# CCM_0010.net
KiCad netlist of a schematic drawn in EAGLE
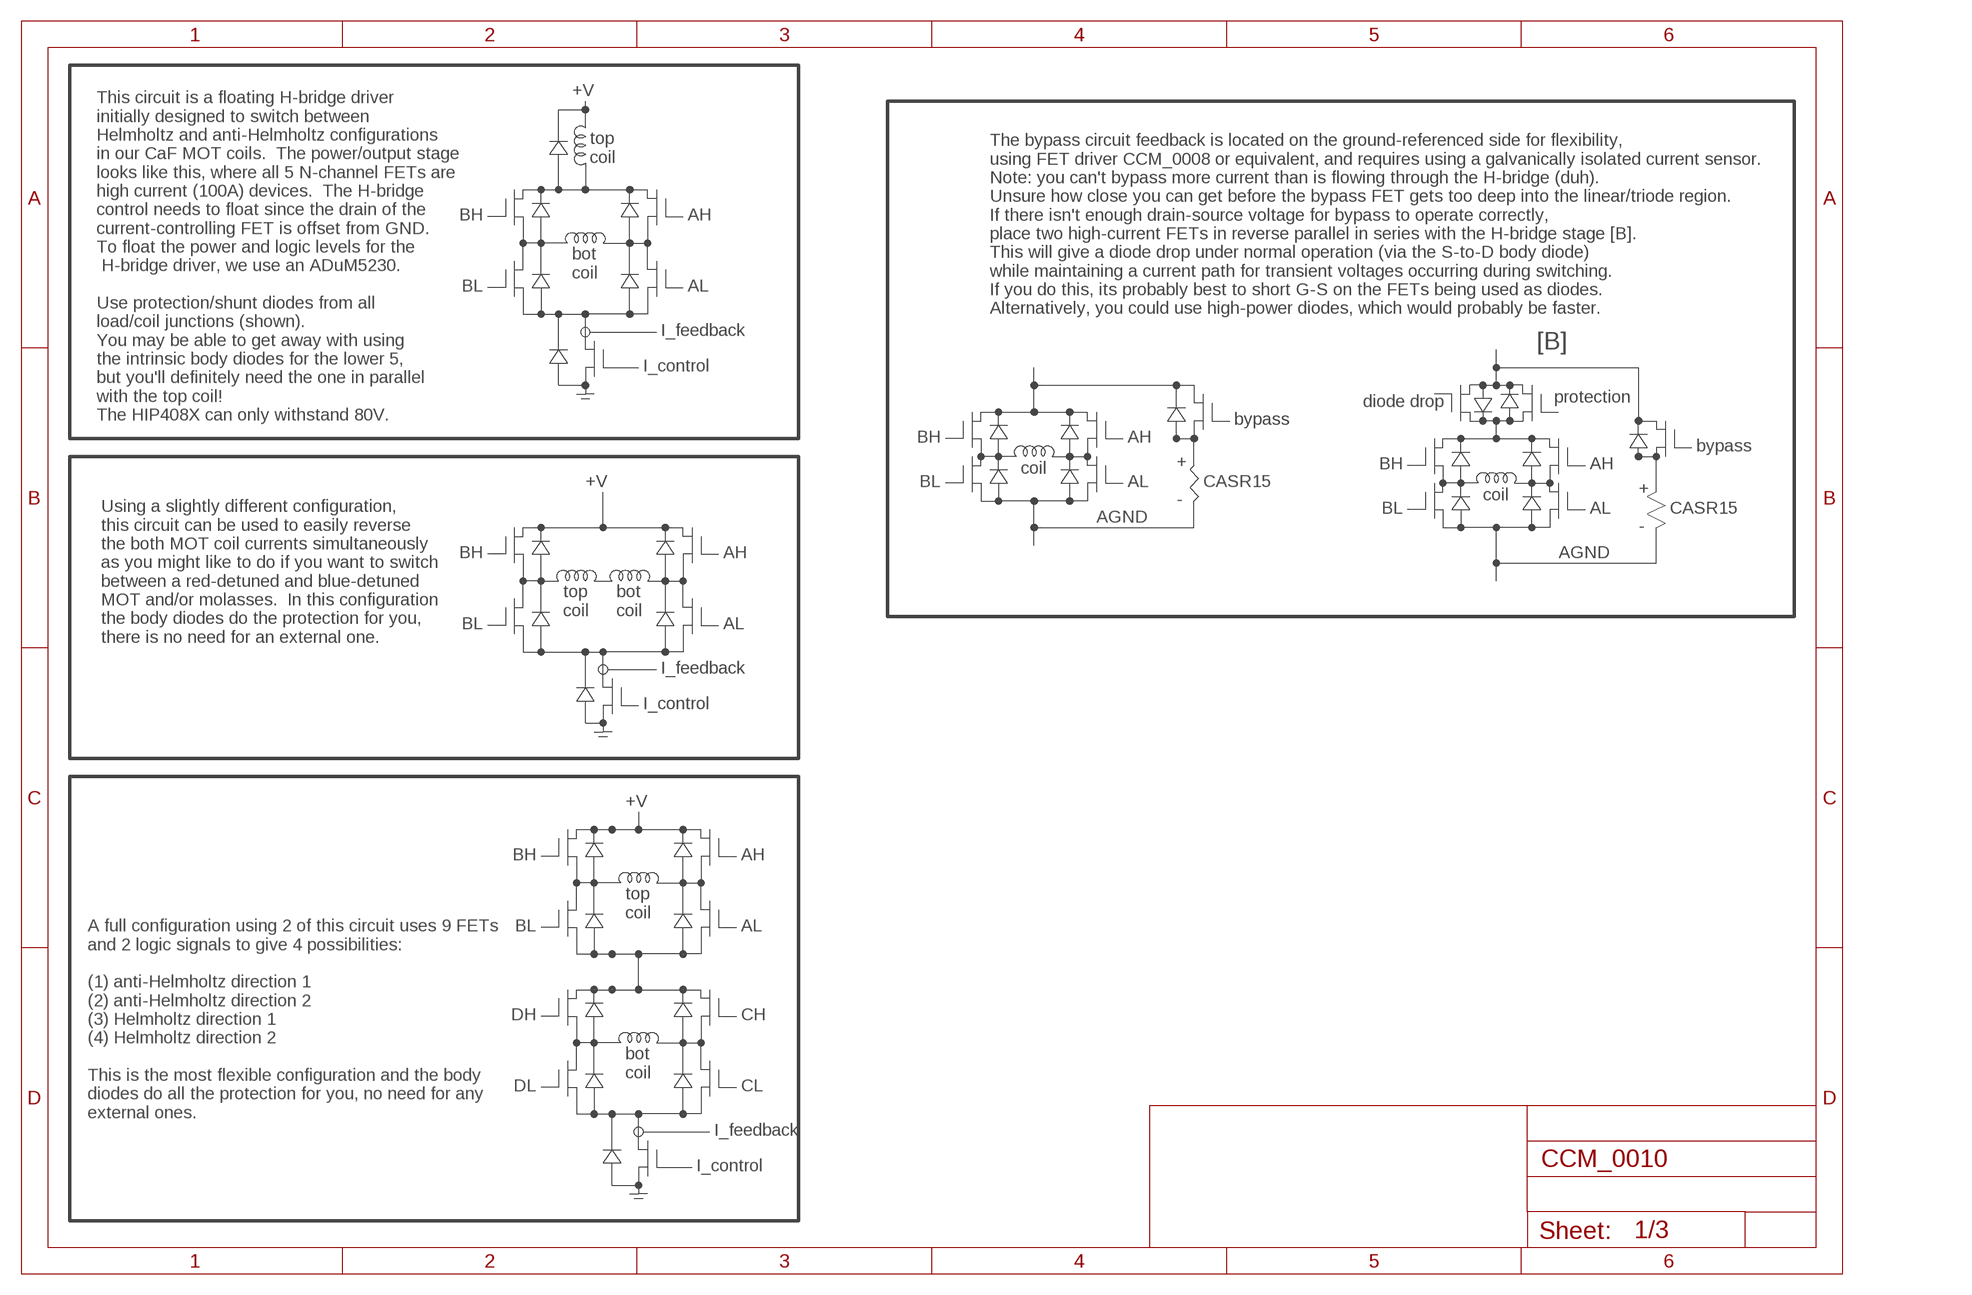
[diagram p0: schematic, sheet 1]
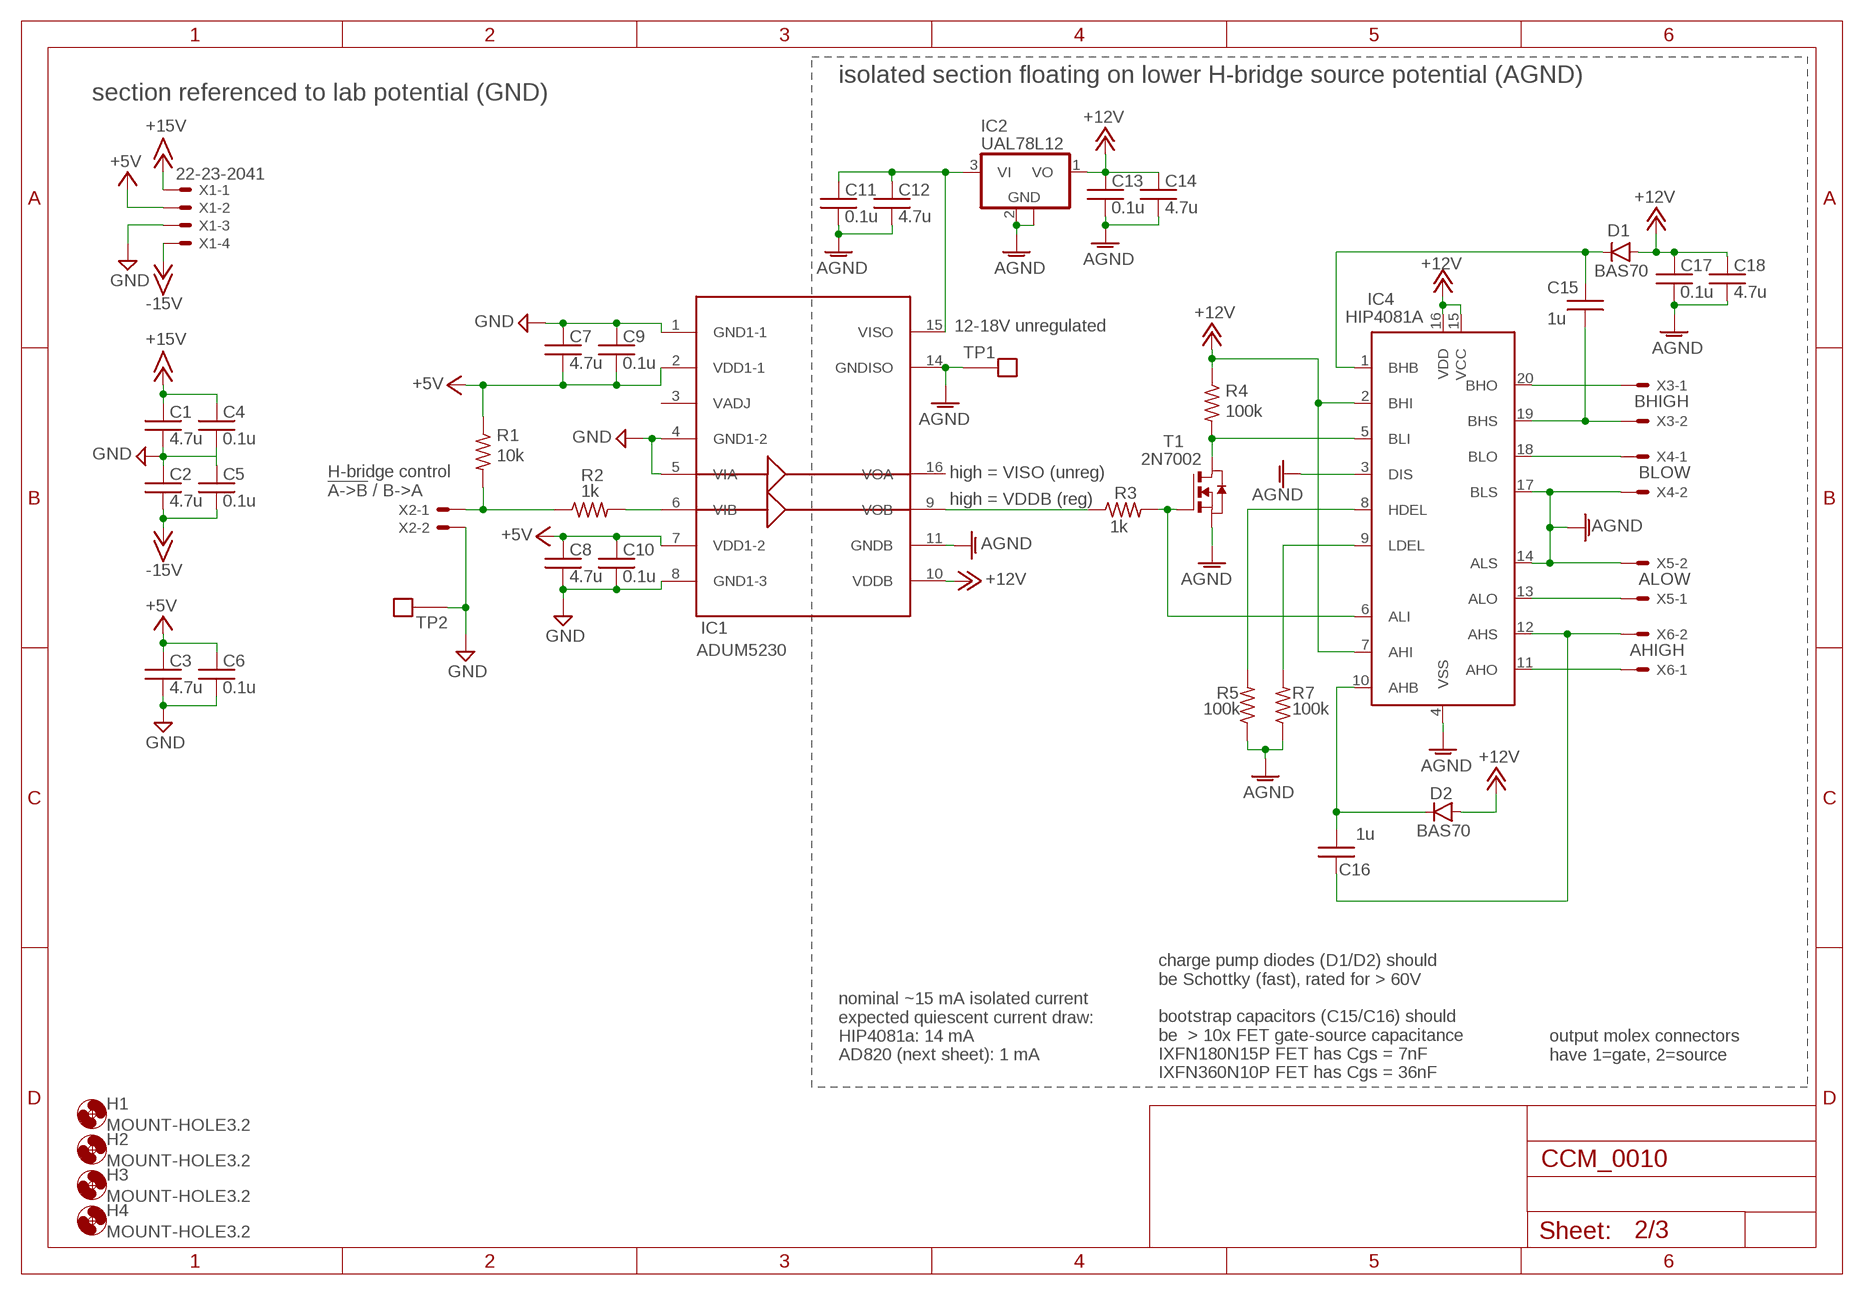
[diagram p1: schematic, sheet 2]
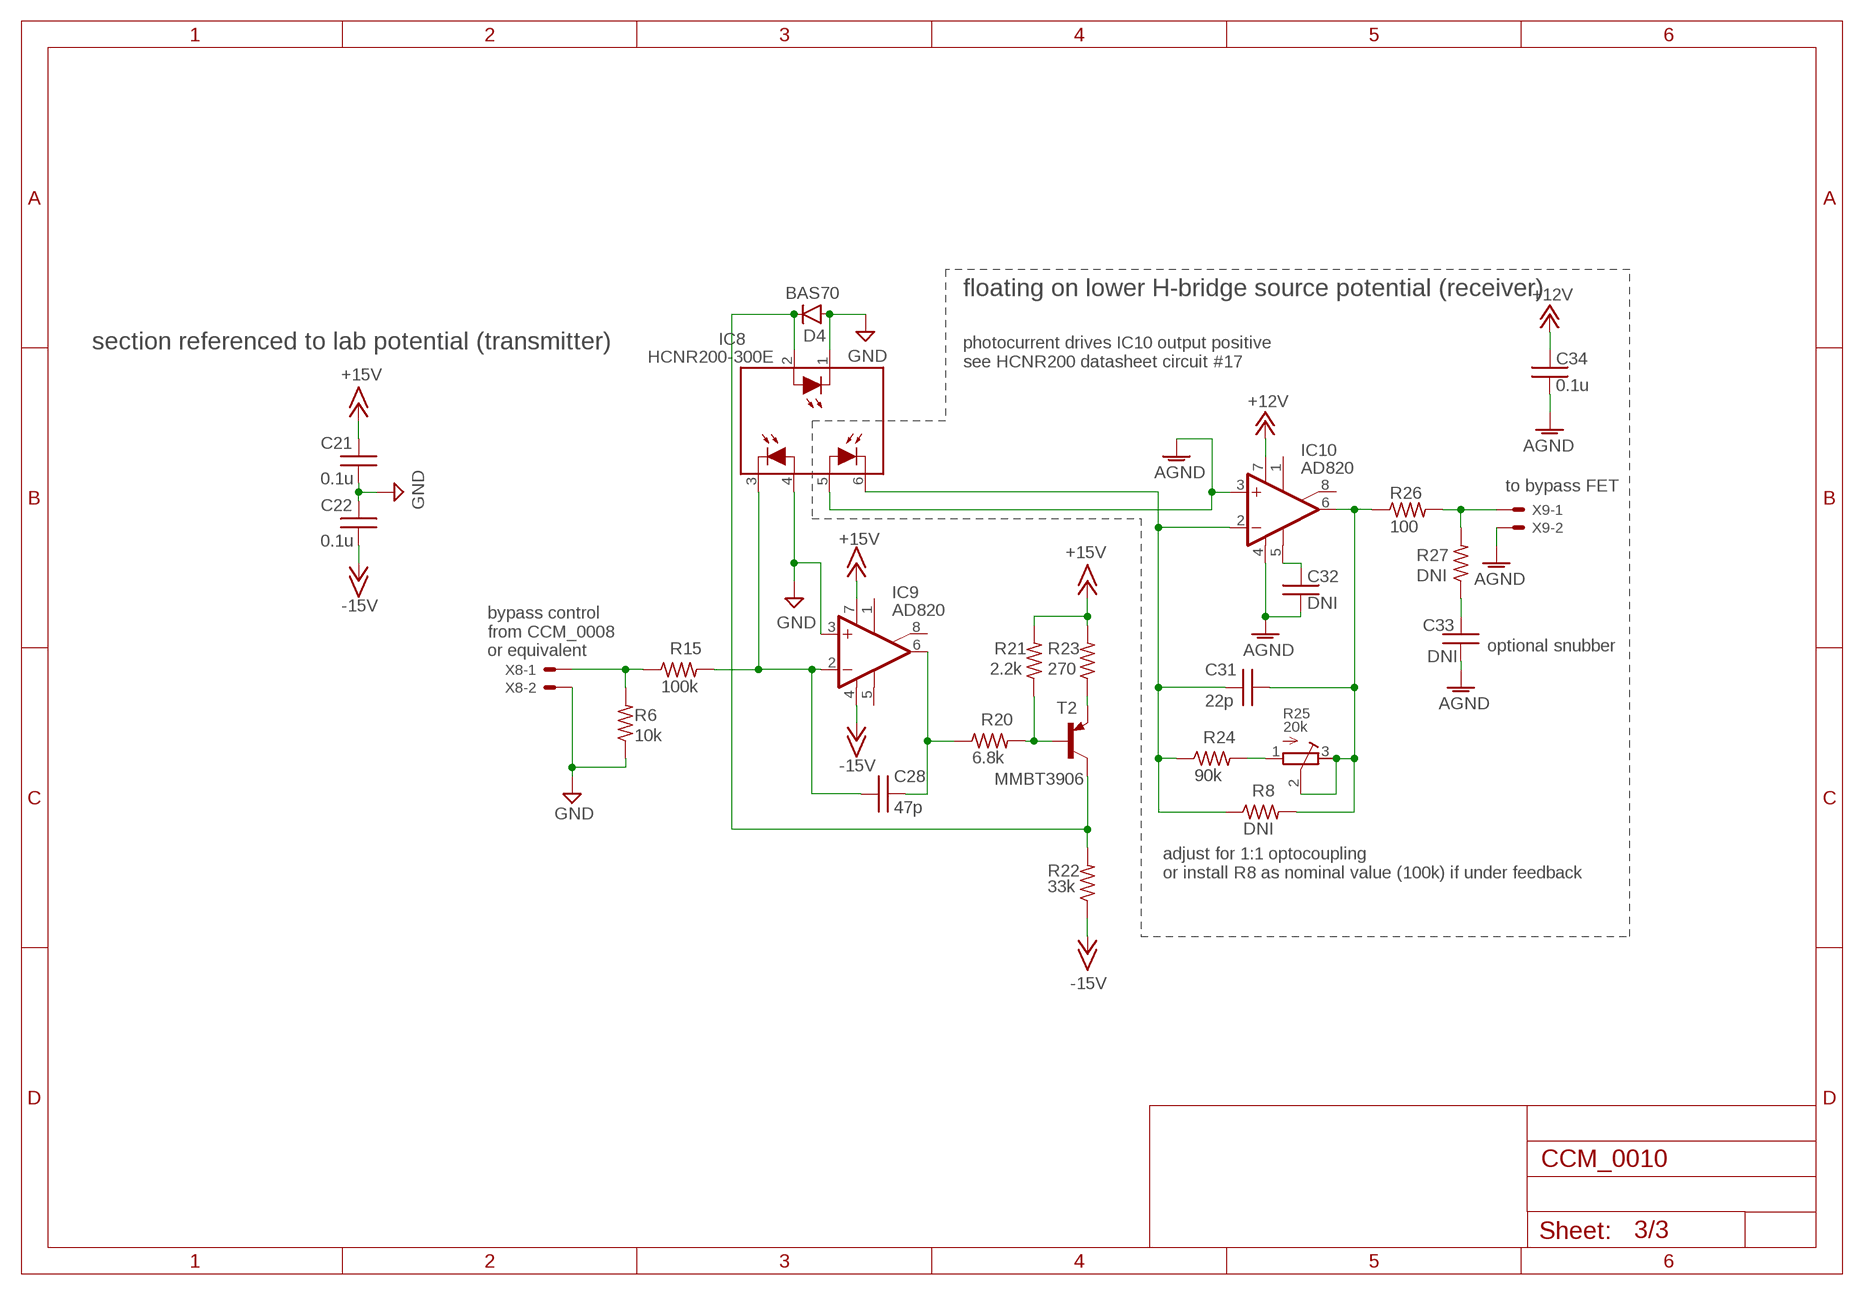
[diagram p2: schematic, sheet 3]

(export (version "E")
  (design (tool "Eeschema 10.0.6"))
  (components
    (comp (ref "C21")
      (value "0.1u")
      (footprint "eagle-import:0603")
      (libsource (lib "eagle-import") (part "C0603"))
    )
    (comp (ref "C22")
      (value "0.1u")
      (footprint "eagle-import:0603")
      (libsource (lib "eagle-import") (part "C0603"))
    )
    (comp (ref "C28")
      (value "47p")
      (footprint "eagle-import:0603")
      (libsource (lib "eagle-import") (part "C0603"))
    )
    (comp (ref "C31")
      (value "22p")
      (footprint "eagle-import:0603")
      (libsource (lib "eagle-import") (part "C0603"))
    )
    (comp (ref "C32")
      (value "DNI")
      (footprint "eagle-import:0603")
      (libsource (lib "eagle-import") (part "C0603"))
    )
    (comp (ref "C33")
      (value "DNI")
      (footprint "eagle-import:0603")
      (libsource (lib "eagle-import") (part "C0603"))
    )
    (comp (ref "C34")
      (value "0.1u")
      (footprint "eagle-import:0603")
      (libsource (lib "eagle-import") (part "C0603"))
    )
    (comp (ref "D4")
      (value "BAS70")
      (footprint "eagle-import:SOT23-3")
      (libsource (lib "eagle-import") (part "DIODESOT23"))
    )
    (comp (ref "IC8")
      (value "HCNR200-300E")
      (footprint "eagle-import:DIP8-400")
      (libsource (lib "eagle-import") (part "HCNR20-300E0"))
    )
    (comp (ref "IC9")
      (value "AD820")
      (footprint "eagle-import:SO08")
      (libsource (lib "eagle-import") (part "OP07RC"))
    )
    (comp (ref "IC10")
      (value "AD820")
      (footprint "eagle-import:SO08")
      (libsource (lib "eagle-import") (part "OP07RC"))
    )
    (comp (ref "R6")
      (value "10k")
      (footprint "eagle-import:0603")
      (libsource (lib "eagle-import") (part "R0603"))
    )
    (comp (ref "R8")
      (value "DNI")
      (footprint "eagle-import:0603")
      (libsource (lib "eagle-import") (part "R0603"))
    )
    (comp (ref "R15")
      (value "100k")
      (footprint "eagle-import:0603")
      (libsource (lib "eagle-import") (part "R0603"))
    )
    (comp (ref "R20")
      (value "6.8k")
      (footprint "eagle-import:0603")
      (libsource (lib "eagle-import") (part "R0603"))
    )
    (comp (ref "R21")
      (value "2.2k")
      (footprint "eagle-import:0603")
      (libsource (lib "eagle-import") (part "R0603"))
    )
    (comp (ref "R22")
      (value "33k")
      (footprint "eagle-import:0603")
      (libsource (lib "eagle-import") (part "R0603"))
    )
    (comp (ref "R23")
      (value "270")
      (footprint "eagle-import:0603")
      (libsource (lib "eagle-import") (part "R0603"))
    )
    (comp (ref "R24")
      (value "90k")
      (footprint "eagle-import:0603")
      (libsource (lib "eagle-import") (part "R0603"))
    )
    (comp (ref "R25")
      (value "20k")
      (footprint "eagle-import:RTRIM3224W")
      (libsource (lib "eagle-import") (part "R-TRIMM3224W"))
    )
    (comp (ref "R26")
      (value "100")
      (footprint "eagle-import:0603")
      (libsource (lib "eagle-import") (part "R0603"))
    )
    (comp (ref "R27")
      (value "DNI")
      (footprint "eagle-import:0603")
      (libsource (lib "eagle-import") (part "R0603"))
    )
    (comp (ref "T2")
      (value "MMBT3906")
      (footprint "eagle-import:SOT23-BEC")
      (libsource (lib "eagle-import") (part "-PNP-SOT23-BECMMBT3906LT1"))
    )
    (comp (ref "X8")
      (value "22-23-2021")
      (footprint "eagle-import:22-23-2021")
      (fields (field (name "MF") "MOLEX"))
      (libsource (lib "eagle-import") (part "22-23-2021"))
    )
    (comp (ref "X9")
      (value "22-23-2021")
      (footprint "eagle-import:22-23-2021")
      (fields (field (name "MF") "MOLEX"))
      (libsource (lib "eagle-import") (part "22-23-2021"))
    )
    (comp (ref "C1")
      (value "4.7u")
      (footprint "eagle-import:0603")
      (libsource (lib "eagle-import") (part "C0603"))
    )
    (comp (ref "C2")
      (value "4.7u")
      (footprint "eagle-import:0603")
      (libsource (lib "eagle-import") (part "C0603"))
    )
    (comp (ref "C3")
      (value "4.7u")
      (footprint "eagle-import:0603")
      (libsource (lib "eagle-import") (part "C0603"))
    )
    (comp (ref "C4")
      (value "0.1u")
      (footprint "eagle-import:0603")
      (libsource (lib "eagle-import") (part "C0603"))
    )
    (comp (ref "C5")
      (value "0.1u")
      (footprint "eagle-import:0603")
      (libsource (lib "eagle-import") (part "C0603"))
    )
    (comp (ref "C6")
      (value "0.1u")
      (footprint "eagle-import:0603")
      (libsource (lib "eagle-import") (part "C0603"))
    )
    (comp (ref "C7")
      (value "4.7u")
      (footprint "eagle-import:0603")
      (libsource (lib "eagle-import") (part "C0603"))
    )
    (comp (ref "C8")
      (value "4.7u")
      (footprint "eagle-import:0603")
      (libsource (lib "eagle-import") (part "C0603"))
    )
    (comp (ref "C9")
      (value "0.1u")
      (footprint "eagle-import:0603")
      (libsource (lib "eagle-import") (part "C0603"))
    )
    (comp (ref "C10")
      (value "0.1u")
      (footprint "eagle-import:0603")
      (libsource (lib "eagle-import") (part "C0603"))
    )
    (comp (ref "C11")
      (value "0.1u")
      (footprint "eagle-import:0603")
      (libsource (lib "eagle-import") (part "C0603"))
    )
    (comp (ref "C12")
      (value "4.7u")
      (footprint "eagle-import:0603")
      (libsource (lib "eagle-import") (part "C0603"))
    )
    (comp (ref "C13")
      (value "0.1u")
      (footprint "eagle-import:0603")
      (libsource (lib "eagle-import") (part "C0603"))
    )
    (comp (ref "C14")
      (value "4.7u")
      (footprint "eagle-import:0603")
      (libsource (lib "eagle-import") (part "C0603"))
    )
    (comp (ref "C15")
      (value "1u")
      (footprint "eagle-import:0603")
      (libsource (lib "eagle-import") (part "C0603"))
    )
    (comp (ref "C16")
      (value "1u")
      (footprint "eagle-import:0603")
      (libsource (lib "eagle-import") (part "C0603"))
    )
    (comp (ref "C17")
      (value "0.1u")
      (footprint "eagle-import:0603")
      (libsource (lib "eagle-import") (part "C0603"))
    )
    (comp (ref "C18")
      (value "4.7u")
      (footprint "eagle-import:0603")
      (libsource (lib "eagle-import") (part "C0603"))
    )
    (comp (ref "D1")
      (value "BAS70")
      (footprint "eagle-import:SOT23-3")
      (libsource (lib "eagle-import") (part "DIODESOT23"))
    )
    (comp (ref "D2")
      (value "BAS70")
      (footprint "eagle-import:SOT23-3")
      (libsource (lib "eagle-import") (part "DIODESOT23"))
    )
    (comp (ref "H1")
      (value "MOUNT-HOLE3.2")
      (footprint "eagle-import:3,2")
      (libsource (lib "eagle-import") (part "MOUNT-HOLE3.2"))
    )
    (comp (ref "H2")
      (value "MOUNT-HOLE3.2")
      (footprint "eagle-import:3,2")
      (libsource (lib "eagle-import") (part "MOUNT-HOLE3.2"))
    )
    (comp (ref "H3")
      (value "MOUNT-HOLE3.2")
      (footprint "eagle-import:3,2")
      (libsource (lib "eagle-import") (part "MOUNT-HOLE3.2"))
    )
    (comp (ref "H4")
      (value "MOUNT-HOLE3.2")
      (footprint "eagle-import:3,2")
      (libsource (lib "eagle-import") (part "MOUNT-HOLE3.2"))
    )
    (comp (ref "IC1")
      (value "ADUM5230")
      (footprint "eagle-import:SO16W")
      (libsource (lib "eagle-import") (part "ADUM5230"))
    )
    (comp (ref "IC2")
      (value "UAL78L12")
      (footprint "eagle-import:SOT89")
      (libsource (lib "eagle-import") (part "78LF12"))
    )
    (comp (ref "IC4")
      (value "HIP4081A")
      (footprint "eagle-import:SO20")
      (libsource (lib "eagle-import") (part "HIP4081A"))
    )
    (comp (ref "R1")
      (value "10k")
      (footprint "eagle-import:0603")
      (libsource (lib "eagle-import") (part "R0603"))
    )
    (comp (ref "R2")
      (value "1k")
      (footprint "eagle-import:0603")
      (libsource (lib "eagle-import") (part "R0603"))
    )
    (comp (ref "R3")
      (value "1k")
      (footprint "eagle-import:0603")
      (libsource (lib "eagle-import") (part "R0603"))
    )
    (comp (ref "R4")
      (value "100k")
      (footprint "eagle-import:0603")
      (libsource (lib "eagle-import") (part "R0603"))
    )
    (comp (ref "R5")
      (value "100k")
      (footprint "eagle-import:0603")
      (libsource (lib "eagle-import") (part "R0603"))
    )
    (comp (ref "R7")
      (value "100k")
      (footprint "eagle-import:0603")
      (libsource (lib "eagle-import") (part "R0603"))
    )
    (comp (ref "T1")
      (value "2N7002")
      (footprint "eagle-import:SOT-23")
      (libsource (lib "eagle-import") (part "NMOSSOT23"))
    )
    (comp (ref "TP1")
      (value "TESTPOINT")
      (footprint "eagle-import:TESTPOINT")
      (libsource (lib "eagle-import") (part "TESTPOINT"))
    )
    (comp (ref "TP2")
      (value "TESTPOINT")
      (footprint "eagle-import:TESTPOINT")
      (libsource (lib "eagle-import") (part "TESTPOINT"))
    )
    (comp (ref "X1")
      (value "22-23-2041")
      (footprint "eagle-import:22-23-2041")
      (fields (field (name "MF") "MOLEX"))
      (libsource (lib "eagle-import") (part "22-23-2041"))
    )
    (comp (ref "X2")
      (value "22-23-2021")
      (footprint "eagle-import:22-23-2021")
      (fields (field (name "MF") "MOLEX"))
      (libsource (lib "eagle-import") (part "22-23-2021"))
    )
    (comp (ref "X3")
      (value "22-23-2021")
      (footprint "eagle-import:22-23-2021")
      (fields (field (name "MF") "MOLEX"))
      (libsource (lib "eagle-import") (part "22-23-2021"))
    )
    (comp (ref "X4")
      (value "22-23-2021")
      (footprint "eagle-import:22-23-2021")
      (fields (field (name "MF") "MOLEX"))
      (libsource (lib "eagle-import") (part "22-23-2021"))
    )
    (comp (ref "X5")
      (value "22-23-2021")
      (footprint "eagle-import:22-23-2021")
      (fields (field (name "MF") "MOLEX"))
      (libsource (lib "eagle-import") (part "22-23-2021"))
    )
    (comp (ref "X6")
      (value "22-23-2021")
      (footprint "eagle-import:22-23-2021")
      (fields (field (name "MF") "MOLEX"))
      (libsource (lib "eagle-import") (part "22-23-2021"))
    )
  )
  (nets
    (net (code "1") (name "+5V") (class "Default")
      (node (ref "C10") (pin "1") (pinfunction "1_1") (pintype "passive"))
      (node (ref "C3") (pin "1") (pinfunction "1_1") (pintype "passive"))
      (node (ref "C6") (pin "1") (pinfunction "1_1") (pintype "passive"))
      (node (ref "C7") (pin "2") (pinfunction "2_2") (pintype "passive"))
      (node (ref "C8") (pin "1") (pinfunction "1_1") (pintype "passive"))
      (node (ref "C9") (pin "2") (pinfunction "2_2") (pintype "passive"))
      (node (ref "IC1") (pin "2") (pinfunction "VDD1-1_2") (pintype "bidirectional"))
      (node (ref "IC1") (pin "7") (pinfunction "VDD1-2_7") (pintype "bidirectional"))
      (node (ref "R1") (pin "1") (pinfunction "1_1") (pintype "passive"))
      (node (ref "X1") (pin "2") (pinfunction "S_2") (pintype "passive"))
    )
    (net (code "2") (name "+12V") (class "Default")
      (node (ref "C13") (pin "1") (pinfunction "1_1") (pintype "passive"))
      (node (ref "C14") (pin "1") (pinfunction "1_1") (pintype "passive"))
      (node (ref "C17") (pin "1") (pinfunction "1_1") (pintype "passive"))
      (node (ref "C18") (pin "1") (pinfunction "1_1") (pintype "passive"))
      (node (ref "C34") (pin "1") (pinfunction "1_1") (pintype "passive"))
      (node (ref "D1") (pin "1") (pinfunction "A_1") (pintype "passive"))
      (node (ref "D2") (pin "1") (pinfunction "A_1") (pintype "passive"))
      (node (ref "IC1") (pin "10") (pinfunction "VDDB_10") (pintype "bidirectional"))
      (node (ref "IC10") (pin "7") (pinfunction "V+_7") (pintype "power_in"))
      (node (ref "IC2") (pin "1") (pinfunction "VO_1") (pintype "passive"))
      (node (ref "IC4") (pin "15") (pinfunction "VCC_15") (pintype "input"))
      (node (ref "IC4") (pin "16") (pinfunction "VDD_16") (pintype "power_in"))
      (node (ref "IC4") (pin "2") (pinfunction "BHI_2") (pintype "input"))
      (node (ref "IC4") (pin "7") (pinfunction "AHI_7") (pintype "input"))
      (node (ref "R4") (pin "1") (pinfunction "1_1") (pintype "passive"))
    )
    (net (code "3") (name "+15V") (class "Default")
      (node (ref "C1") (pin "1") (pinfunction "1_1") (pintype "passive"))
      (node (ref "C21") (pin "2") (pinfunction "2_2") (pintype "passive"))
      (node (ref "C4") (pin "1") (pinfunction "1_1") (pintype "passive"))
      (node (ref "IC9") (pin "7") (pinfunction "V+_7") (pintype "power_in"))
      (node (ref "R21") (pin "2") (pinfunction "2_2") (pintype "passive"))
      (node (ref "R23") (pin "2") (pinfunction "2_2") (pintype "passive"))
      (node (ref "X1") (pin "1") (pinfunction "S_1") (pintype "passive"))
    )
    (net (code "4") (name "-15V") (class "Default")
      (node (ref "C2") (pin "2") (pinfunction "2_2") (pintype "passive"))
      (node (ref "C22") (pin "1") (pinfunction "1_1") (pintype "passive"))
      (node (ref "C5") (pin "2") (pinfunction "2_2") (pintype "passive"))
      (node (ref "IC9") (pin "4") (pinfunction "V-_4") (pintype "power_in"))
      (node (ref "R22") (pin "1") (pinfunction "1_1") (pintype "passive"))
      (node (ref "X1") (pin "4") (pinfunction "S_4") (pintype "passive"))
    )
    (net (code "5") (name "AGND") (class "Default")
      (node (ref "C11") (pin "2") (pinfunction "2_2") (pintype "passive"))
      (node (ref "C12") (pin "2") (pinfunction "2_2") (pintype "passive"))
      (node (ref "C13") (pin "2") (pinfunction "2_2") (pintype "passive"))
      (node (ref "C14") (pin "2") (pinfunction "2_2") (pintype "passive"))
      (node (ref "C17") (pin "2") (pinfunction "2_2") (pintype "passive"))
      (node (ref "C18") (pin "2") (pinfunction "2_2") (pintype "passive"))
      (node (ref "C32") (pin "2") (pinfunction "2_2") (pintype "passive"))
      (node (ref "C33") (pin "2") (pinfunction "2_2") (pintype "passive"))
      (node (ref "C34") (pin "2") (pinfunction "2_2") (pintype "passive"))
      (node (ref "IC1") (pin "11") (pinfunction "GNDB_11") (pintype "bidirectional"))
      (node (ref "IC1") (pin "14") (pinfunction "GNDISO_14") (pintype "bidirectional"))
      (node (ref "IC10") (pin "3") (pinfunction "+IN_3") (pintype "input"))
      (node (ref "IC10") (pin "4") (pinfunction "V-_4") (pintype "power_in"))
      (node (ref "IC2") (pin "2") (pinfunction "GND_2") (pintype "passive"))
      (node (ref "IC2") (pin "2@1") (pinfunction "GND_2@1") (pintype "passive"))
      (node (ref "IC4") (pin "14") (pinfunction "ALS_14") (pintype "passive"))
      (node (ref "IC4") (pin "17") (pinfunction "BLS_17") (pintype "passive"))
      (node (ref "IC4") (pin "3") (pinfunction "DIS_3") (pintype "input"))
      (node (ref "IC4") (pin "4") (pinfunction "VSS_4") (pintype "power_in"))
      (node (ref "IC8") (pin "5") (pinfunction "A2_5") (pintype "passive"))
      (node (ref "R5") (pin "1") (pinfunction "1_1") (pintype "passive"))
      (node (ref "R7") (pin "1") (pinfunction "1_1") (pintype "passive"))
      (node (ref "T1") (pin "2") (pinfunction "S_2") (pintype "passive"))
      (node (ref "TP1") (pin "P$1") (pinfunction "P$1_P$1") (pintype "bidirectional"))
      (node (ref "X4") (pin "2") (pinfunction "S_2") (pintype "passive"))
      (node (ref "X5") (pin "2") (pinfunction "S_2") (pintype "passive"))
      (node (ref "X9") (pin "2") (pinfunction "S_2") (pintype "passive"))
    )
    (net (code "6") (name "GND") (class "Default")
      (node (ref "C1") (pin "2") (pinfunction "2_2") (pintype "passive"))
      (node (ref "C10") (pin "2") (pinfunction "2_2") (pintype "passive"))
      (node (ref "C2") (pin "1") (pinfunction "1_1") (pintype "passive"))
      (node (ref "C21") (pin "1") (pinfunction "1_1") (pintype "passive"))
      (node (ref "C22") (pin "2") (pinfunction "2_2") (pintype "passive"))
      (node (ref "C3") (pin "2") (pinfunction "2_2") (pintype "passive"))
      (node (ref "C4") (pin "2") (pinfunction "2_2") (pintype "passive"))
      (node (ref "C5") (pin "1") (pinfunction "1_1") (pintype "passive"))
      (node (ref "C6") (pin "2") (pinfunction "2_2") (pintype "passive"))
      (node (ref "C7") (pin "1") (pinfunction "1_1") (pintype "passive"))
      (node (ref "C8") (pin "2") (pinfunction "2_2") (pintype "passive"))
      (node (ref "C9") (pin "1") (pinfunction "1_1") (pintype "passive"))
      (node (ref "D4") (pin "1") (pinfunction "A_1") (pintype "passive"))
      (node (ref "IC1") (pin "1") (pinfunction "GND1-1_1") (pintype "bidirectional"))
      (node (ref "IC1") (pin "4") (pinfunction "GND1-2_4") (pintype "bidirectional"))
      (node (ref "IC1") (pin "5") (pinfunction "VIA_5") (pintype "bidirectional"))
      (node (ref "IC1") (pin "8") (pinfunction "GND1-3_8") (pintype "bidirectional"))
      (node (ref "IC8") (pin "1") (pinfunction "C_1") (pintype "passive"))
      (node (ref "IC8") (pin "4") (pinfunction "A1_4") (pintype "passive"))
      (node (ref "IC9") (pin "3") (pinfunction "+IN_3") (pintype "input"))
      (node (ref "R6") (pin "1") (pinfunction "1_1") (pintype "passive"))
      (node (ref "TP2") (pin "P$1") (pinfunction "P$1_P$1") (pintype "bidirectional"))
      (node (ref "X1") (pin "3") (pinfunction "S_3") (pintype "passive"))
      (node (ref "X2") (pin "2") (pinfunction "S_2") (pintype "passive"))
      (node (ref "X8") (pin "2") (pinfunction "S_2") (pintype "passive"))
    )
    (net (code "7") (name "Net-(C33-Pad1)") (class "Default")
      (node (ref "C33") (pin "1") (pinfunction "1_1") (pintype "passive"))
      (node (ref "R27") (pin "1") (pinfunction "1_1") (pintype "passive"))
    )
    (net (code "8") (name "Net-(D1-C)") (class "Default")
      (node (ref "C15") (pin "2") (pinfunction "2_2") (pintype "passive"))
      (node (ref "D1") (pin "3") (pinfunction "C_3") (pintype "passive"))
      (node (ref "IC4") (pin "1") (pinfunction "BHB_1") (pintype "input"))
    )
    (net (code "9") (name "Net-(D2-C)") (class "Default")
      (node (ref "C16") (pin "1") (pinfunction "1_1") (pintype "passive"))
      (node (ref "D2") (pin "3") (pinfunction "C_3") (pintype "passive"))
      (node (ref "IC4") (pin "10") (pinfunction "AHB_10") (pintype "input"))
    )
    (net (code "10") (name "Net-(D4-C)") (class "Default")
      (node (ref "D4") (pin "3") (pinfunction "C_3") (pintype "passive"))
      (node (ref "IC8") (pin "2") (pinfunction "A_2") (pintype "passive"))
      (node (ref "R22") (pin "2") (pinfunction "2_2") (pintype "passive"))
      (node (ref "T2") (pin "C") (pinfunction "C_C") (pintype "passive"))
    )
    (net (code "11") (name "Net-(IC1-VIB)") (class "Default")
      (node (ref "IC1") (pin "6") (pinfunction "VIB_6") (pintype "bidirectional"))
      (node (ref "R2") (pin "2") (pinfunction "2_2") (pintype "passive"))
    )
    (net (code "12") (name "Net-(IC1-VISO)") (class "Default")
      (node (ref "C11") (pin "1") (pinfunction "1_1") (pintype "passive"))
      (node (ref "C12") (pin "1") (pinfunction "1_1") (pintype "passive"))
      (node (ref "IC1") (pin "15") (pinfunction "VISO_15") (pintype "bidirectional"))
      (node (ref "IC2") (pin "3") (pinfunction "VI_3") (pintype "input"))
    )
    (net (code "13") (name "Net-(IC1-VOB)") (class "Default")
      (node (ref "IC1") (pin "9") (pinfunction "VOB_9") (pintype "bidirectional"))
      (node (ref "R3") (pin "1") (pinfunction "1_1") (pintype "passive"))
    )
    (net (code "14") (name "Net-(IC4-AHO)") (class "Default")
      (node (ref "IC4") (pin "11") (pinfunction "AHO_11") (pintype "output"))
      (node (ref "X6") (pin "1") (pinfunction "S_1") (pintype "passive"))
    )
    (net (code "15") (name "Net-(IC4-AHS)") (class "Default")
      (node (ref "C16") (pin "2") (pinfunction "2_2") (pintype "passive"))
      (node (ref "IC4") (pin "12") (pinfunction "AHS_12") (pintype "input"))
      (node (ref "X6") (pin "2") (pinfunction "S_2") (pintype "passive"))
    )
    (net (code "16") (name "Net-(IC4-ALI)") (class "Default")
      (node (ref "IC4") (pin "6") (pinfunction "ALI_6") (pintype "input"))
      (node (ref "R3") (pin "2") (pinfunction "2_2") (pintype "passive"))
      (node (ref "T1") (pin "3") (pinfunction "G_3") (pintype "passive"))
    )
    (net (code "17") (name "Net-(IC4-ALO)") (class "Default")
      (node (ref "IC4") (pin "13") (pinfunction "ALO_13") (pintype "output"))
      (node (ref "X5") (pin "1") (pinfunction "S_1") (pintype "passive"))
    )
    (net (code "18") (name "Net-(IC4-BHO)") (class "Default")
      (node (ref "IC4") (pin "20") (pinfunction "BHO_20") (pintype "output"))
      (node (ref "X3") (pin "1") (pinfunction "S_1") (pintype "passive"))
    )
    (net (code "19") (name "Net-(IC4-BHS)") (class "Default")
      (node (ref "C15") (pin "1") (pinfunction "1_1") (pintype "passive"))
      (node (ref "IC4") (pin "19") (pinfunction "BHS_19") (pintype "input"))
      (node (ref "X3") (pin "2") (pinfunction "S_2") (pintype "passive"))
    )
    (net (code "20") (name "Net-(IC4-BLI)") (class "Default")
      (node (ref "IC4") (pin "5") (pinfunction "BLI_5") (pintype "input"))
      (node (ref "R4") (pin "2") (pinfunction "2_2") (pintype "passive"))
      (node (ref "T1") (pin "1") (pinfunction "D_1") (pintype "passive"))
    )
    (net (code "21") (name "Net-(IC4-BLO)") (class "Default")
      (node (ref "IC4") (pin "18") (pinfunction "BLO_18") (pintype "output"))
      (node (ref "X4") (pin "1") (pinfunction "S_1") (pintype "passive"))
    )
    (net (code "22") (name "Net-(IC4-HDEL)") (class "Default")
      (node (ref "IC4") (pin "8") (pinfunction "HDEL_8") (pintype "input"))
      (node (ref "R5") (pin "2") (pinfunction "2_2") (pintype "passive"))
    )
    (net (code "23") (name "Net-(IC4-LDEL)") (class "Default")
      (node (ref "IC4") (pin "9") (pinfunction "LDEL_9") (pintype "input"))
      (node (ref "R7") (pin "2") (pinfunction "2_2") (pintype "passive"))
    )
    (net (code "24") (name "Net-(IC8-C1)") (class "Default")
      (node (ref "C28") (pin "2") (pinfunction "2_2") (pintype "passive"))
      (node (ref "IC8") (pin "3") (pinfunction "C1_3") (pintype "passive"))
      (node (ref "IC9") (pin "2") (pinfunction "-IN_2") (pintype "input"))
      (node (ref "R15") (pin "2") (pinfunction "2_2") (pintype "passive"))
    )
    (net (code "25") (name "Net-(IC9-OUT)") (class "Default")
      (node (ref "C28") (pin "1") (pinfunction "1_1") (pintype "passive"))
      (node (ref "IC9") (pin "6") (pinfunction "OUT_6") (pintype "output"))
      (node (ref "R20") (pin "1") (pinfunction "1_1") (pintype "passive"))
    )
    (net (code "26") (name "Net-(IC10--IN)") (class "Default")
      (node (ref "C31") (pin "2") (pinfunction "2_2") (pintype "passive"))
      (node (ref "IC10") (pin "2") (pinfunction "-IN_2") (pintype "input"))
      (node (ref "IC8") (pin "6") (pinfunction "C2_6") (pintype "passive"))
      (node (ref "R24") (pin "1") (pinfunction "1_1") (pintype "passive"))
      (node (ref "R8") (pin "1") (pinfunction "1_1") (pintype "passive"))
    )
    (net (code "27") (name "Net-(IC10-OPT)") (class "Default")
      (node (ref "C32") (pin "1") (pinfunction "1_1") (pintype "passive"))
      (node (ref "IC10") (pin "5") (pinfunction "OPT_5") (pintype "passive"))
    )
    (net (code "28") (name "Net-(IC10-OUT)") (class "Default")
      (node (ref "C31") (pin "1") (pinfunction "1_1") (pintype "passive"))
      (node (ref "IC10") (pin "6") (pinfunction "OUT_6") (pintype "output"))
      (node (ref "R25") (pin "2") (pinfunction "S_2") (pintype "passive"))
      (node (ref "R25") (pin "3") (pinfunction "E_3") (pintype "passive"))
      (node (ref "R26") (pin "1") (pinfunction "1_1") (pintype "passive"))
      (node (ref "R8") (pin "2") (pinfunction "2_2") (pintype "passive"))
    )
    (net (code "29") (name "Net-(R20-Pad2)") (class "Default")
      (node (ref "R20") (pin "2") (pinfunction "2_2") (pintype "passive"))
      (node (ref "R21") (pin "1") (pinfunction "1_1") (pintype "passive"))
      (node (ref "T2") (pin "B") (pinfunction "B_B") (pintype "passive"))
    )
    (net (code "30") (name "Net-(R23-Pad1)") (class "Default")
      (node (ref "R23") (pin "1") (pinfunction "1_1") (pintype "passive"))
      (node (ref "T2") (pin "E") (pinfunction "E_E") (pintype "passive"))
    )
    (net (code "31") (name "Net-(R25-A)") (class "Default")
      (node (ref "R24") (pin "2") (pinfunction "2_2") (pintype "passive"))
      (node (ref "R25") (pin "1") (pinfunction "A_1") (pintype "passive"))
    )
    (net (code "32") (name "Net-(X2A-S)") (class "Default")
      (node (ref "R1") (pin "2") (pinfunction "2_2") (pintype "passive"))
      (node (ref "R2") (pin "1") (pinfunction "1_1") (pintype "passive"))
      (node (ref "X2") (pin "1") (pinfunction "S_1") (pintype "passive"))
    )
    (net (code "33") (name "Net-(X8A-S)") (class "Default")
      (node (ref "R15") (pin "1") (pinfunction "1_1") (pintype "passive"))
      (node (ref "R6") (pin "2") (pinfunction "2_2") (pintype "passive"))
      (node (ref "X8") (pin "1") (pinfunction "S_1") (pintype "passive"))
    )
    (net (code "34") (name "Net-(X9A-S)") (class "Default")
      (node (ref "R26") (pin "2") (pinfunction "2_2") (pintype "passive"))
      (node (ref "R27") (pin "2") (pinfunction "2_2") (pintype "passive"))
      (node (ref "X9") (pin "1") (pinfunction "S_1") (pintype "passive"))
    )
    (net (code "35") (name "unconnected-(IC1-VADJ-Pad3)") (class "Default")
      (node (ref "IC1") (pin "3") (pinfunction "VADJ_3") (pintype "bidirectional"))
    )
    (net (code "36") (name "unconnected-(IC1-VOA-Pad16)") (class "Default")
      (node (ref "IC1") (pin "16") (pinfunction "VOA_16") (pintype "bidirectional"))
    )
    (net (code "37") (name "unconnected-(IC9-ON1-Pad1)") (class "Default")
      (node (ref "IC9") (pin "1") (pinfunction "ON1_1") (pintype "passive"))
    )
    (net (code "38") (name "unconnected-(IC9-ON2-Pad8)") (class "Default")
      (node (ref "IC9") (pin "8") (pinfunction "ON2_8") (pintype "passive"))
    )
    (net (code "39") (name "unconnected-(IC9-OPT-Pad5)") (class "Default")
      (node (ref "IC9") (pin "5") (pinfunction "OPT_5") (pintype "passive"))
    )
    (net (code "40") (name "unconnected-(IC10-ON1-Pad1)") (class "Default")
      (node (ref "IC10") (pin "1") (pinfunction "ON1_1") (pintype "passive"))
    )
    (net (code "41") (name "unconnected-(IC10-ON2-Pad8)") (class "Default")
      (node (ref "IC10") (pin "8") (pinfunction "ON2_8") (pintype "passive"))
    )
  )
)
